# zFocus_remote_ferq.net
KiCad netlist of a schematic drawn in EasyEDA Pro
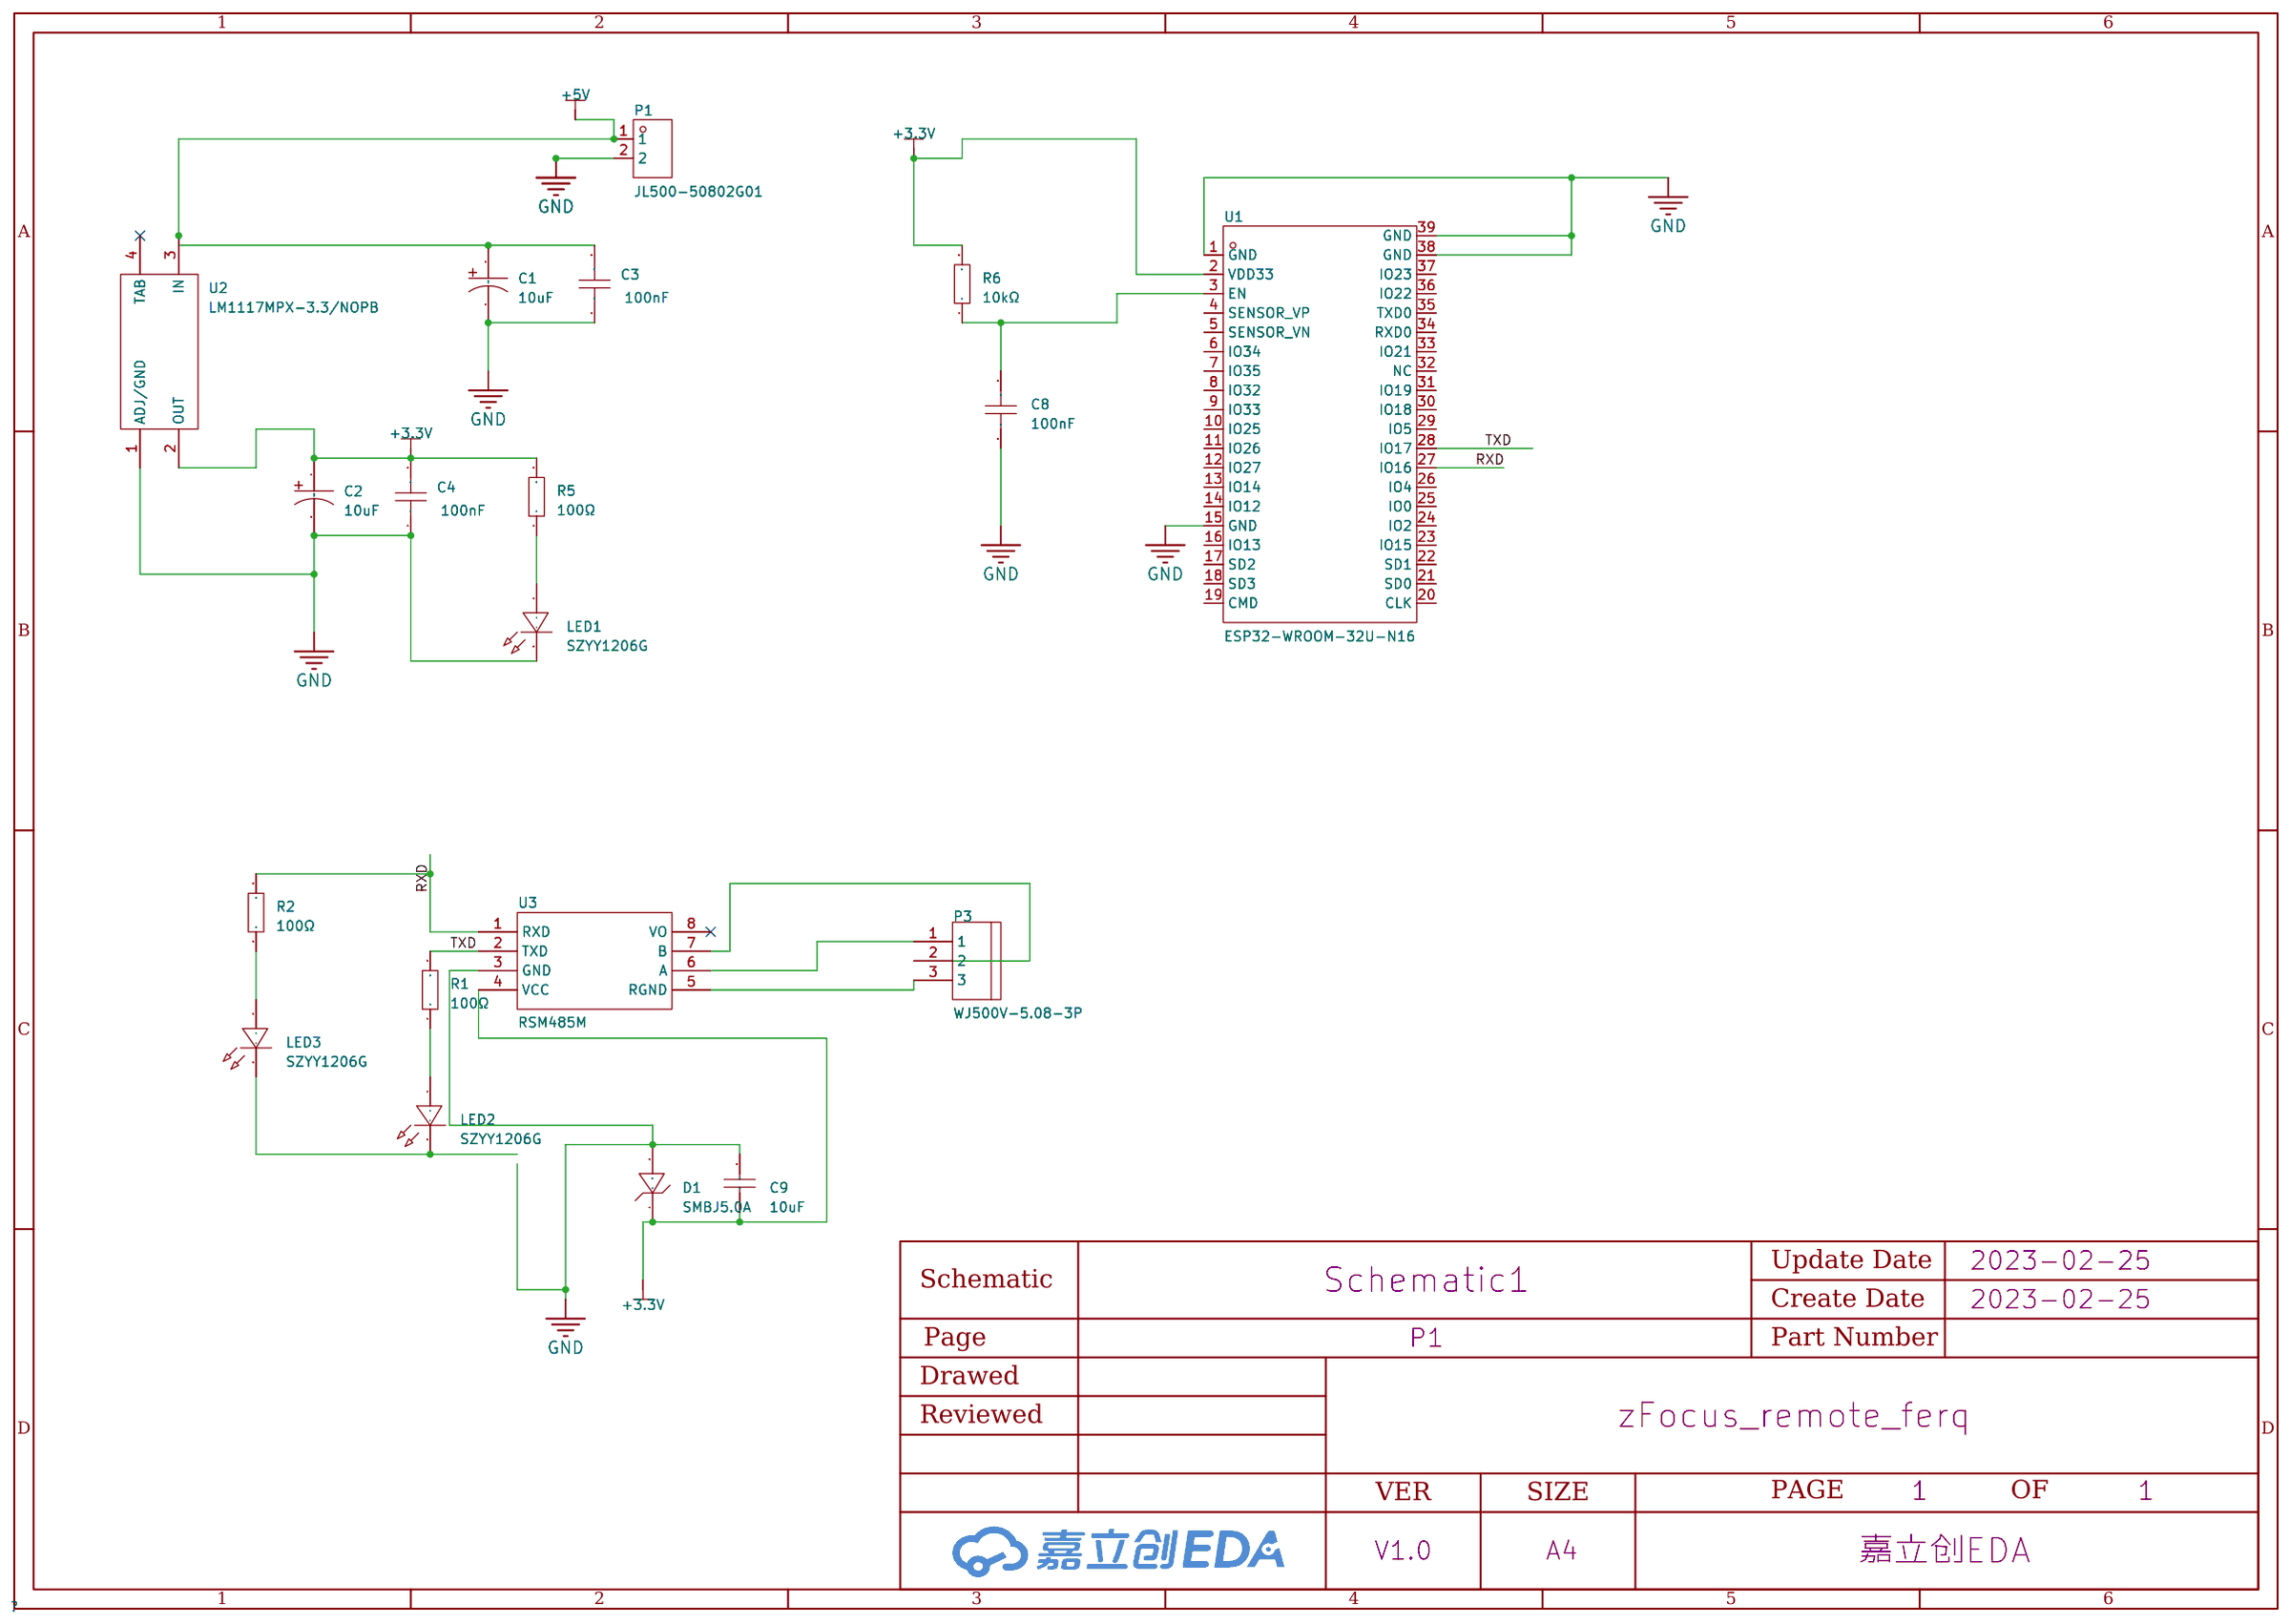
[diagram p0: schematic sheet]

(export (version "E")
  (design (tool "Eeschema 10.0.6"))
  (components
    (comp (ref "C1")
      (value "10uF")
      (footprint "easyedapro:CAP-SMD_BD4.0-L4.3-W4.3-LS5.0-FD")
      (fields (field (name "Manufacturer Part") "RVT1V100M0405") (field (name "Manufacturer") "HONOR(荣誉)"))
      (libsource (lib "easyedapro") (part "RVT1V100M0405"))
    )
    (comp (ref "C2")
      (value "10uF")
      (footprint "easyedapro:CAP-SMD_BD4.0-L4.3-W4.3-LS5.0-FD")
      (fields (field (name "Manufacturer Part") "RVT1V100M0405") (field (name "Manufacturer") "HONOR(荣誉)"))
      (libsource (lib "easyedapro") (part "RVT1V100M0405"))
    )
    (comp (ref "C3")
      (value "100nF")
      (footprint "easyedapro:C1206")
      (description "温度系数:X7R;容值:100nF;精度:±20%;额定电压:50V;")
      (fields
        (field (name "Manufacturer Part") "TCC1206X7R104M500DT")
        (field (name "Manufacturer") "CCTC(三环)")
      )
      (libsource (lib "easyedapro") (part "TCC1206X7R104M500DT"))
    )
    (comp (ref "C4")
      (value "100nF")
      (footprint "easyedapro:C1206")
      (description "温度系数:X7R;容值:100nF;精度:±20%;额定电压:50V;")
      (fields
        (field (name "Manufacturer Part") "TCC1206X7R104M500DT")
        (field (name "Manufacturer") "CCTC(三环)")
      )
      (libsource (lib "easyedapro") (part "TCC1206X7R104M500DT"))
    )
    (comp (ref "C8")
      (value "100nF")
      (footprint "easyedapro:C1206")
      (description "容值:100nF;精度:±10%;额定电压:50V;材质(温度系数):X7R;")
      (fields
        (field (name "Manufacturer Part") "CC1206KRX7R9BB104")
        (field (name "Manufacturer") "YAGEO(国巨)")
      )
      (libsource (lib "easyedapro") (part "CC1206KRX7R9BB104"))
    )
    (comp (ref "C9")
      (value "10uF")
      (footprint "easyedapro:C1206")
      (description "容值:10uF;精度:±10%;额定电压:25V;材质(温度系数):X5R;")
      (fields
        (field (name "Manufacturer Part") "CL31A106KAHNNNE")
        (field (name "Manufacturer") "SAMSUNG(三星)")
      )
      (libsource (lib "easyedapro") (part "CL31A106KAHNNNE"))
    )
    (comp (ref "D1")
      (value "SMBJ5.0A")
      (footprint "easyedapro:SMB_L4.6-W3.6-LS5.3-RD")
      (description "极性:单向;反向截止电压(Vrwm):5V;击穿电压:6.4V;峰值脉冲电流(Ipp)@10/1000s:-;最大钳位电压:9.2V;峰值脉冲功率(Ppp)@10/1000s:600W;")
      (fields (field (name "Manufacturer") "Littelfuse(美国力特)"))
      (libsource (lib "easyedapro") (part "SMBJ5.0A_C83333"))
    )
    (comp (ref "LED1")
      (value "SZYY1206G")
      (footprint "easyedapro:LED1206-R-RD")
      (description "发光颜色:翠绿;")
      (fields (field (name "Manufacturer") "yongyu(永裕光电)"))
      (libsource (lib "easyedapro") (part "SZYY1206G"))
    )
    (comp (ref "LED2")
      (value "SZYY1206G")
      (footprint "easyedapro:LED1206-R-RD")
      (description "发光颜色:翠绿;")
      (fields (field (name "Manufacturer") "yongyu(永裕光电)"))
      (libsource (lib "easyedapro") (part "SZYY1206G"))
    )
    (comp (ref "LED3")
      (value "SZYY1206G")
      (footprint "easyedapro:LED1206-R-RD")
      (description "发光颜色:翠绿;")
      (fields (field (name "Manufacturer") "yongyu(永裕光电)"))
      (libsource (lib "easyedapro") (part "SZYY1206G"))
    )
    (comp (ref "P1")
      (value "JL500-50802G01")
      (footprint "easyedapro:CONN-TH_2P-P5.08_JL500-50002G01")
      (fields (field (name "Manufacturer") "JILN(锦凌)"))
      (libsource (lib "easyedapro") (part "JL500-50802G01_C709041"))
    )
    (comp (ref "P3")
      (value "WJ500V-5.08-3P")
      (footprint "easyedapro:CONN-TH_3P-P5.00_WJ500V-5.08-3P")
      (fields (field (name "Manufacturer") "KANGNEX(康奈克斯电气)"))
      (libsource (lib "easyedapro") (part "WJ500V-5.08-3P-14-00A"))
    )
    (comp (ref "R1")
      (value "100Ω")
      (footprint "easyedapro:R1206")
      (description "电阻类型:厚膜电阻;阻值:100Ω;精度:±1%;功率:250mW;温度系数:±100ppm/℃;最大工作电压:200V;工作温度范围:-55℃~+155℃;")
      (fields
        (field (name "Manufacturer Part") "1206W4F1000T5E")
        (field (name "Manufacturer") "UNI-ROYAL(厚声)")
      )
      (libsource (lib "easyedapro") (part "1206W4F1000T5E"))
    )
    (comp (ref "R2")
      (value "100Ω")
      (footprint "easyedapro:R1206")
      (description "电阻类型:厚膜电阻;阻值:100Ω;精度:±1%;功率:250mW;温度系数:±100ppm/℃;最大工作电压:200V;工作温度范围:-55℃~+155℃;")
      (fields
        (field (name "Manufacturer Part") "1206W4F1000T5E")
        (field (name "Manufacturer") "UNI-ROYAL(厚声)")
      )
      (libsource (lib "easyedapro") (part "1206W4F1000T5E"))
    )
    (comp (ref "R5")
      (value "100Ω")
      (footprint "easyedapro:R1206")
      (description "电阻类型:厚膜电阻;阻值:100Ω;精度:±1%;功率:250mW;温度系数:±100ppm/℃;最大工作电压:200V;工作温度范围:-55℃~+155℃;")
      (fields
        (field (name "Manufacturer Part") "1206W4F1000T5E")
        (field (name "Manufacturer") "UNI-ROYAL(厚声)")
      )
      (libsource (lib "easyedapro") (part "1206W4F1000T5E"))
    )
    (comp (ref "R6")
      (value "10kΩ")
      (footprint "easyedapro:R1206")
      (description "电阻类型:厚膜电阻;阻值:10kΩ;精度:±1%;功率:250mW;温度系数:±100ppm/℃;最大工作电压:200V;工作温度范围:-55℃~+155℃;")
      (fields
        (field (name "Manufacturer Part") "1206W4F1002T5E")
        (field (name "Manufacturer") "UNI-ROYAL(厚声)")
      )
      (libsource (lib "easyedapro") (part "1206W4F1002T5E"))
    )
    (comp (ref "U1")
      (value "ESP32-WROOM-32U-N16")
      (footprint "easyedapro:WIFIM-SMD_39P-L19.2-W18.0-P1.27")
      (fields (field (name "Manufacturer") "ESPRESSIF(乐鑫)"))
      (libsource (lib "easyedapro") (part "ESP32-WROOM-32U(16MB)"))
    )
    (comp (ref "U2")
      (value "LM1117MPX-3.3/NOPB")
      (footprint "easyedapro:SOT-223-3_L6.5-W3.4-P2.30-LS7.0-BR")
      (description "输出类型:固定;输出极性:正;输出通道数:1;最大输入电压:15V;输出电压:3.3V;压差:1.2V@(800mA);输出电流:800mA;电源纹波抑制比(PSRR):75dB@(120Hz);")
      (fields (field (name "Manufacturer") "TI(德州仪器)"))
      (libsource (lib "easyedapro") (part "LM1117MPX-3.3/NOPB"))
    )
    (comp (ref "U3")
      (value "RSM485M")
      (footprint "easyedapro:COMM-TH_RSM485M")
      (description "数据速率:500Kbps;节点数:64;静态电流:27mA;电源电压:3.15V~5.25V;静电保护:否;隔离:2500V;自动流控:否;")
      (fields (field (name "Manufacturer") "ZLG(致远电子)"))
      (libsource (lib "easyedapro") (part "RSM485M"))
    )
  )
  (nets
    (net (code "1") (name "+3.3V") (class "Default")
      (node (ref "C2") (pin "1") (pinfunction "1_1") (pintype "input"))
      (node (ref "C4") (pin "2") (pinfunction "2_2") (pintype "input"))
      (node (ref "C9") (pin "1") (pinfunction "1_1") (pintype "input"))
      (node (ref "D1") (pin "1") (pinfunction "1_1") (pintype "input"))
      (node (ref "R5") (pin "2") (pinfunction "2_2") (pintype "input"))
      (node (ref "R6") (pin "2") (pinfunction "2_2") (pintype "input"))
      (node (ref "U1") (pin "2") (pinfunction "VDD33_2") (pintype "input"))
      (node (ref "U2") (pin "2") (pinfunction "OUT_2") (pintype "input"))
      (node (ref "U3") (pin "4") (pinfunction "VCC_4") (pintype "input"))
    )
    (net (code "2") (name "+5V") (class "Default")
      (node (ref "C1") (pin "1") (pinfunction "1_1") (pintype "input"))
      (node (ref "C3") (pin "2") (pinfunction "2_2") (pintype "input"))
      (node (ref "P1") (pin "1") (pinfunction "1_1") (pintype "input"))
      (node (ref "U2") (pin "3") (pinfunction "IN_3") (pintype "input"))
    )
    (net (code "3") (name "/RXD") (class "Default")
      (node (ref "R2") (pin "2") (pinfunction "2_2") (pintype "input"))
      (node (ref "U1") (pin "27") (pinfunction "IO16_27") (pintype "input"))
      (node (ref "U3") (pin "1") (pinfunction "RXD_1") (pintype "input"))
    )
    (net (code "4") (name "/TXD") (class "Default")
      (node (ref "R1") (pin "2") (pinfunction "2_2") (pintype "input"))
      (node (ref "U1") (pin "28") (pinfunction "IO17_28") (pintype "input"))
      (node (ref "U3") (pin "2") (pinfunction "TXD_2") (pintype "input"))
    )
    (net (code "5") (name "GND") (class "Default")
      (node (ref "C1") (pin "2") (pinfunction "2_2") (pintype "input"))
      (node (ref "C2") (pin "2") (pinfunction "2_2") (pintype "input"))
      (node (ref "C3") (pin "1") (pinfunction "1_1") (pintype "input"))
      (node (ref "C4") (pin "1") (pinfunction "1_1") (pintype "input"))
      (node (ref "C8") (pin "1") (pinfunction "1_1") (pintype "input"))
      (node (ref "C9") (pin "2") (pinfunction "2_2") (pintype "input"))
      (node (ref "D1") (pin "2") (pinfunction "2_2") (pintype "input"))
      (node (ref "LED1") (pin "2") (pinfunction "-_2") (pintype "input"))
      (node (ref "P1") (pin "2") (pinfunction "2_2") (pintype "input"))
      (node (ref "U1") (pin "1") (pinfunction "GND_1") (pintype "input"))
      (node (ref "U1") (pin "15") (pinfunction "GND_15") (pintype "input"))
      (node (ref "U1") (pin "38") (pinfunction "GND_38") (pintype "input"))
      (node (ref "U1") (pin "39") (pinfunction "GND_39") (pintype "input"))
      (node (ref "U2") (pin "1") (pinfunction "ADJ/GND_1") (pintype "input"))
      (node (ref "U3") (pin "3") (pinfunction "GND_3") (pintype "input"))
    )
    (net (code "6") (name "Net-(LED1-+)") (class "Default")
      (node (ref "LED1") (pin "1") (pinfunction "+_1") (pintype "input"))
      (node (ref "R5") (pin "1") (pinfunction "1_1") (pintype "input"))
    )
    (net (code "7") (name "Net-(LED2-+)") (class "Default")
      (node (ref "LED2") (pin "1") (pinfunction "+_1") (pintype "input"))
      (node (ref "R1") (pin "1") (pinfunction "1_1") (pintype "input"))
    )
    (net (code "8") (name "Net-(LED2--)") (class "Default")
      (node (ref "LED2") (pin "2") (pinfunction "-_2") (pintype "input"))
      (node (ref "LED3") (pin "2") (pinfunction "-_2") (pintype "input"))
    )
    (net (code "9") (name "Net-(LED3-+)") (class "Default")
      (node (ref "LED3") (pin "1") (pinfunction "+_1") (pintype "input"))
      (node (ref "R2") (pin "1") (pinfunction "1_1") (pintype "input"))
    )
    (net (code "10") (name "Net-(U1-EN)") (class "Default")
      (node (ref "C8") (pin "2") (pinfunction "2_2") (pintype "input"))
      (node (ref "R6") (pin "1") (pinfunction "1_1") (pintype "input"))
      (node (ref "U1") (pin "3") (pinfunction "EN_3") (pintype "input"))
    )
    (net (code "11") (name "Net-(U3-A)") (class "Default")
      (node (ref "P3") (pin "1") (pinfunction "1_1") (pintype "input"))
      (node (ref "U3") (pin "6") (pinfunction "A_6") (pintype "input"))
    )
    (net (code "12") (name "Net-(U3-B)") (class "Default")
      (node (ref "P3") (pin "2") (pinfunction "2_2") (pintype "input"))
      (node (ref "U3") (pin "7") (pinfunction "B_7") (pintype "input"))
    )
    (net (code "13") (name "Net-(U3-RGND)") (class "Default")
      (node (ref "P3") (pin "3") (pinfunction "3_3") (pintype "input"))
      (node (ref "U3") (pin "5") (pinfunction "RGND_5") (pintype "input"))
    )
    (net (code "14") (name "unconnected-(U1-CLK-Pad20)") (class "Default")
      (node (ref "U1") (pin "20") (pinfunction "CLK_20") (pintype "input"))
    )
    (net (code "15") (name "unconnected-(U1-CMD-Pad19)") (class "Default")
      (node (ref "U1") (pin "19") (pinfunction "CMD_19") (pintype "input"))
    )
    (net (code "16") (name "unconnected-(U1-IO0-Pad25)") (class "Default")
      (node (ref "U1") (pin "25") (pinfunction "IO0_25") (pintype "input"))
    )
    (net (code "17") (name "unconnected-(U1-IO2-Pad24)") (class "Default")
      (node (ref "U1") (pin "24") (pinfunction "IO2_24") (pintype "input"))
    )
    (net (code "18") (name "unconnected-(U1-IO4-Pad26)") (class "Default")
      (node (ref "U1") (pin "26") (pinfunction "IO4_26") (pintype "input"))
    )
    (net (code "19") (name "unconnected-(U1-IO5-Pad29)") (class "Default")
      (node (ref "U1") (pin "29") (pinfunction "IO5_29") (pintype "input"))
    )
    (net (code "20") (name "unconnected-(U1-IO12-Pad14)") (class "Default")
      (node (ref "U1") (pin "14") (pinfunction "IO12_14") (pintype "input"))
    )
    (net (code "21") (name "unconnected-(U1-IO13-Pad16)") (class "Default")
      (node (ref "U1") (pin "16") (pinfunction "IO13_16") (pintype "input"))
    )
    (net (code "22") (name "unconnected-(U1-IO14-Pad13)") (class "Default")
      (node (ref "U1") (pin "13") (pinfunction "IO14_13") (pintype "input"))
    )
    (net (code "23") (name "unconnected-(U1-IO15-Pad23)") (class "Default")
      (node (ref "U1") (pin "23") (pinfunction "IO15_23") (pintype "input"))
    )
    (net (code "24") (name "unconnected-(U1-IO18-Pad30)") (class "Default")
      (node (ref "U1") (pin "30") (pinfunction "IO18_30") (pintype "input"))
    )
    (net (code "25") (name "unconnected-(U1-IO19-Pad31)") (class "Default")
      (node (ref "U1") (pin "31") (pinfunction "IO19_31") (pintype "input"))
    )
    (net (code "26") (name "unconnected-(U1-IO21-Pad33)") (class "Default")
      (node (ref "U1") (pin "33") (pinfunction "IO21_33") (pintype "input"))
    )
    (net (code "27") (name "unconnected-(U1-IO22-Pad36)") (class "Default")
      (node (ref "U1") (pin "36") (pinfunction "IO22_36") (pintype "input"))
    )
    (net (code "28") (name "unconnected-(U1-IO23-Pad37)") (class "Default")
      (node (ref "U1") (pin "37") (pinfunction "IO23_37") (pintype "input"))
    )
    (net (code "29") (name "unconnected-(U1-IO25-Pad10)") (class "Default")
      (node (ref "U1") (pin "10") (pinfunction "IO25_10") (pintype "input"))
    )
    (net (code "30") (name "unconnected-(U1-IO26-Pad11)") (class "Default")
      (node (ref "U1") (pin "11") (pinfunction "IO26_11") (pintype "input"))
    )
    (net (code "31") (name "unconnected-(U1-IO27-Pad12)") (class "Default")
      (node (ref "U1") (pin "12") (pinfunction "IO27_12") (pintype "input"))
    )
    (net (code "32") (name "unconnected-(U1-IO32-Pad8)") (class "Default")
      (node (ref "U1") (pin "8") (pinfunction "IO32_8") (pintype "input"))
    )
    (net (code "33") (name "unconnected-(U1-IO33-Pad9)") (class "Default")
      (node (ref "U1") (pin "9") (pinfunction "IO33_9") (pintype "input"))
    )
    (net (code "34") (name "unconnected-(U1-IO34-Pad6)") (class "Default")
      (node (ref "U1") (pin "6") (pinfunction "IO34_6") (pintype "input"))
    )
    (net (code "35") (name "unconnected-(U1-IO35-Pad7)") (class "Default")
      (node (ref "U1") (pin "7") (pinfunction "IO35_7") (pintype "input"))
    )
    (net (code "36") (name "unconnected-(U1-NC-Pad32)") (class "Default")
      (node (ref "U1") (pin "32") (pinfunction "NC_32") (pintype "input"))
    )
    (net (code "37") (name "unconnected-(U1-RXD0-Pad34)") (class "Default")
      (node (ref "U1") (pin "34") (pinfunction "RXD0_34") (pintype "input"))
    )
    (net (code "38") (name "unconnected-(U1-SD0-Pad21)") (class "Default")
      (node (ref "U1") (pin "21") (pinfunction "SD0_21") (pintype "input"))
    )
    (net (code "39") (name "unconnected-(U1-SD1-Pad22)") (class "Default")
      (node (ref "U1") (pin "22") (pinfunction "SD1_22") (pintype "input"))
    )
    (net (code "40") (name "unconnected-(U1-SD2-Pad17)") (class "Default")
      (node (ref "U1") (pin "17") (pinfunction "SD2_17") (pintype "input"))
    )
    (net (code "41") (name "unconnected-(U1-SD3-Pad18)") (class "Default")
      (node (ref "U1") (pin "18") (pinfunction "SD3_18") (pintype "input"))
    )
    (net (code "42") (name "unconnected-(U1-SENSOR_VN-Pad5)") (class "Default")
      (node (ref "U1") (pin "5") (pinfunction "SENSOR_VN_5") (pintype "input"))
    )
    (net (code "43") (name "unconnected-(U1-SENSOR_VP-Pad4)") (class "Default")
      (node (ref "U1") (pin "4") (pinfunction "SENSOR_VP_4") (pintype "input"))
    )
    (net (code "44") (name "unconnected-(U1-TXD0-Pad35)") (class "Default")
      (node (ref "U1") (pin "35") (pinfunction "TXD0_35") (pintype "input"))
    )
    (net (code "45") (name "unconnected-(U2-TAB-Pad4)") (class "Default")
      (node (ref "U2") (pin "4") (pinfunction "TAB_4") (pintype "input+no_connect"))
    )
    (net (code "46") (name "unconnected-(U3-VO-Pad8)") (class "Default")
      (node (ref "U3") (pin "8") (pinfunction "VO_8") (pintype "input+no_connect"))
    )
  )
)
